# PCB_12V5A_60Wascii.net
KiCad netlist of a schematic drawn in Altium Designer
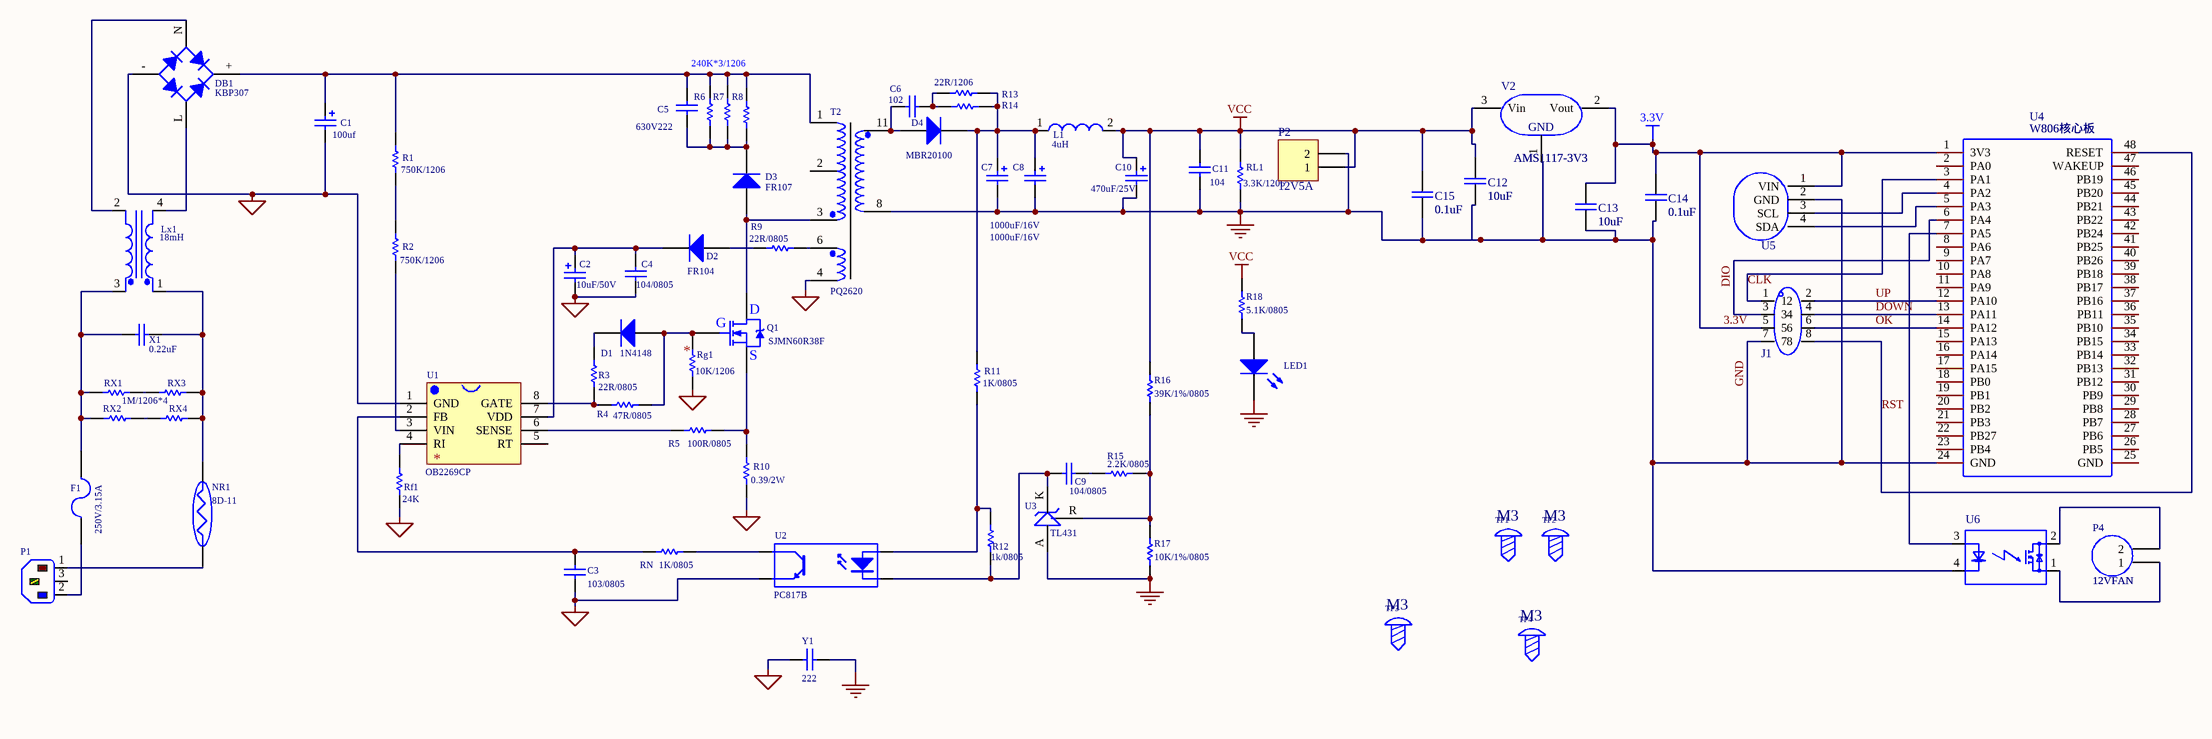
[diagram p0: PCB方案验证板  12V5A 60Wascii.SchDoc]

(export (version "E")
  (design (tool "Eeschema 10.0.6"))
  (components
    (comp (ref "C1")
      (value "100uf")
      (footprint "Cin /400V/56uF Wo")
      (description "Polarized Capacitor (Axial)")
      (fields (field (name "PUBLISHER") "Altium Limited"))
      (libsource (lib "") (part "Cap Pol2_1"))
    )
    (comp (ref "C2")
      (value "10uF/50V")
      (footprint "C Φ5*11 L=2.5")
      (description "Polarized Capacitor (Axial)")
      (fields (field (name "Comment") "47uF/50V") (field (name "PUBLISHER") "Altium Limited"))
      (libsource (lib "") (part "Cap Pol2_1"))
    )
    (comp (ref "C3")
      (value "103/0805")
      (footprint "0805-C")
      (description "Capacitor")
      (fields (field (name "PUBLISHER") "Altium Limited"))
      (libsource (lib "Miscellaneous Devices") (part "Cap"))
    )
    (comp (ref "C4")
      (value "104/0805")
      (footprint "0805-C")
      (description "Capacitor")
      (fields (field (name "PUBLISHER") "Altium Limited"))
      (libsource (lib "Miscellaneous Devices") (part "Cap"))
    )
    (comp (ref "C5")
      (value "630V222")
      (footprint "CBB=7.5MM")
      (description "Capacitor")
      (fields (field (name "PUBLISHER") "Altium Limited"))
      (libsource (lib "Miscellaneous Devices") (part "Cap"))
    )
    (comp (ref "C6")
      (value "102")
      (footprint "1206-C")
      (description "Capacitor")
      (fields (field (name "Comment") "472") (field (name "PUBLISHER") "Altium Limited"))
      (libsource (lib "Miscellaneous Devices") (part "Cap"))
    )
    (comp (ref "C7")
      (value "1000uF/16V")
      (footprint "C 1000UF/16V")
      (description "Polarized Capacitor (Axial)")
      (fields (field (name "PUBLISHER") "Altium Limited"))
      (libsource (lib "Miscellaneous Devices") (part "Cap Pol2"))
    )
    (comp (ref "C8")
      (value "1000uF/16V")
      (footprint "C 1000UF/16V")
      (description "Polarized Capacitor (Axial)")
      (fields (field (name "PUBLISHER") "Altium Limited"))
      (libsource (lib "Miscellaneous Devices") (part "Cap Pol2"))
    )
    (comp (ref "C9")
      (value "104/0805")
      (footprint "0805-C")
      (description "Capacitor")
      (fields (field (name "PUBLISHER") "Altium Limited"))
      (libsource (lib "Miscellaneous Devices") (part "Cap"))
    )
    (comp (ref "C10")
      (value "470uF/25V")
      (footprint "C= 3.5MM 8*15")
      (description "Polarized Capacitor (Axial)")
      (fields (field (name "PUBLISHER") "Altium Limited"))
      (libsource (lib "") (part "Cap Pol2_1"))
    )
    (comp (ref "C11")
      (value "104")
      (footprint "1206-C")
      (description "Capacitor")
      (fields (field (name "PUBLISHER") "Altium Limited"))
      (libsource (lib "Miscellaneous Devices") (part "Cap"))
    )
    (comp (ref "C12")
      (value "10uF")
      (footprint "0805-C")
      (fields (field (name "NAME") "10uF"))
      (libsource (lib "") (part "root_1_CAP-SMT__1"))
    )
    (comp (ref "C13")
      (value "10uF")
      (footprint "0805-C")
      (fields (field (name "NAME") "10uF"))
      (libsource (lib "") (part "root_1_CAP-SMT__1"))
    )
    (comp (ref "C14")
      (value "0.1uF")
      (footprint "0805-C")
      (fields (field (name "NAME") "0.1uF"))
      (libsource (lib "") (part "root_1_CAP-SMT__1"))
    )
    (comp (ref "C15")
      (value "0.1uF")
      (footprint "0805-C")
      (fields (field (name "NAME") "0.1uF"))
      (libsource (lib "altium-import") (part "root_1_CAP-SMT_"))
    )
    (comp (ref "D1")
      (value "1N4148")
      (footprint "D 1N4148")
      (description "Silicon Low Leakage Diode")
      (fields (field (name "PUBLISHER") "Altium Limited"))
      (libsource (lib "") (part "Diode BAS116_1"))
    )
    (comp (ref "D2")
      (value "FR104")
      (footprint "D/SOD123")
      (description "Silicon Low Leakage Diode")
      (fields (field (name "PUBLISHER") "Altium Limited"))
      (libsource (lib "Miscellaneous Devices") (part "Diode BAS116"))
    )
    (comp (ref "D3")
      (value "FR107")
      (footprint "D/SOD123")
      (description "Silicon Low Leakage Diode")
      (fields (field (name "PUBLISHER") "Altium Limited"))
      (libsource (lib "Miscellaneous Devices") (part "Diode BAS116"))
    )
    (comp (ref "D4")
      (value "MBR20100")
      (footprint "D TO-220")
      (description "Silicon Low Leakage Diode")
      (fields (field (name "PUBLISHER") "Altium Limited"))
      (libsource (lib "Miscellaneous Devices") (part "Diode BAS116"))
    )
    (comp (ref "DB1")
      (value "KBP307")
      (footprint "DB D=1.1MM")
      (description "Full Wave Diode Bridge")
      (fields (field (name "PUBLISHER") "Altium Limited"))
      (libsource (lib "Miscellaneous Devices") (part "Bridge1"))
    )
    (comp (ref "F1")
      (value "250V/3.15A")
      (footprint "F 3.15A L=5MM")
      (description "Fuse")
      (fields (field (name "PUBLISHER") "Altium Limited"))
      (libsource (lib "Miscellaneous Devices") (part "Fuse 2"))
    )
    (comp (ref "J1")
      (value "~")
      (footprint "HDR-TH_8P-P2.54-V-F-R2-C4-S2.54-1")
      (fields (field (name "MANUFACTURER PART") "2.54mm,24Doublerowfemale"))
      (libsource (lib "altium-import") (part "root_0_2.54mm,2×4Doublerowfemale_"))
    )
    (comp (ref "L1")
      (value "4uH")
      (footprint "L=7.6MM")
      (description "Inductor")
      (fields (field (name "PUBLISHER") "Altium Limited"))
      (libsource (lib "Miscellaneous Devices") (part "Inductor"))
    )
    (comp (ref "LED1")
      (value "LED1")
      (footprint "C0805")
      (description "Typical RED, GREEN, YELLOW, AMBER GaAs LED")
      (fields (field (name "PUBLISHER") "Altium Limited"))
      (libsource (lib "Miscellaneous Devices") (part "LED2"))
    )
    (comp (ref "Lx1")
      (value "18mH")
      (footprint "LF=6.9MM")
      (description "Transformer (Ideal)")
      (fields (field (name "PUBLISHER") "Altium Limited"))
      (libsource (lib "Miscellaneous Devices") (part "Trans Ideal"))
    )
    (comp (ref "NR1") (value "8D-11") (footprint "NTC=7.5mm") (libsource (lib "12V5A") (part "NTC")))
    (comp (ref "P1")
      (value "Plug AC Male")
      (footprint "KF128-3.81-2P")
      (description "IEC Mains Power Inlet, EN60 320-1 C14 Class I Cold Condition, PC Flange Rear Mount, Chassis Plug")
      (fields (field (name "PUBLISHER") "Altium Limited"))
      (libsource (lib "Miscellaneous Connectors") (part "Plug AC Male"))
    )
    (comp (ref "P2")
      (value "12V5A")
      (footprint "OUT")
      (description "Header, 2-Pin")
      (fields (field (name "PUBLISHER") "Altium Limited"))
      (libsource (lib "Miscellaneous Connectors") (part "Header 2"))
    )
    (comp (ref "P4")
      (value "12VFAN")
      (footprint "OUT")
      (fields (field (name "NAME") "12VFAN") (field (name "PUBLISHER") "Altium Limited"))
      (libsource (lib "altium-import") (part "root_2_12V5A_"))
    )
    (comp (ref "Q1")
      (value "SJMN60R38F")
      (footprint "MOSFET1")
      (description "N-Channel Power MOSFET")
      (fields (field (name "PUBLISHER") "Altium Limited"))
      (libsource (lib "Miscellaneous Devices") (part "NMOS-2"))
    )
    (comp (ref "R1")
      (value "750K/1206")
      (footprint "1206-R")
      (description "Resistor")
      (fields (field (name "PUBLISHER") "Altium Limited"))
      (libsource (lib "Miscellaneous Devices") (part "Res1"))
    )
    (comp (ref "R2")
      (value "750K/1206")
      (footprint "1206-R")
      (description "Resistor")
      (fields (field (name "PUBLISHER") "Altium Limited"))
      (libsource (lib "Miscellaneous Devices") (part "Res1"))
    )
    (comp (ref "R3")
      (value "22R/0805")
      (footprint "0805-R")
      (description "Resistor")
      (fields (field (name "PUBLISHER") "Altium Limited"))
      (libsource (lib "Miscellaneous Devices") (part "Res1"))
    )
    (comp (ref "R4")
      (value "47R/0805")
      (footprint "0805-R")
      (description "Resistor")
      (fields (field (name "PUBLISHER") "Altium Limited"))
      (libsource (lib "Miscellaneous Devices") (part "Res1"))
    )
    (comp (ref "R5")
      (value "100R/0805")
      (footprint "0805-R")
      (description "Resistor")
      (fields (field (name "PUBLISHER") "Altium Limited"))
      (libsource (lib "Miscellaneous Devices") (part "Res1"))
    )
    (comp (ref "R6")
      (value "50K/2510/1W")
      (footprint "1206-R")
      (description "Resistor")
      (fields (field (name "PUBLISHER") "Altium Limited"))
      (libsource (lib "Miscellaneous Devices") (part "Res1"))
    )
    (comp (ref "R7")
      (value "50K/2510/1W")
      (footprint "1206-R")
      (description "Resistor")
      (fields (field (name "PUBLISHER") "Altium Limited"))
      (libsource (lib "Miscellaneous Devices") (part "Res1"))
    )
    (comp (ref "R8")
      (value "50K/2510/1W")
      (footprint "1206-R")
      (description "Resistor")
      (fields (field (name "PUBLISHER") "Altium Limited"))
      (libsource (lib "Miscellaneous Devices") (part "Res1"))
    )
    (comp (ref "R9")
      (value "22R/0805")
      (footprint "0805-R")
      (description "Resistor")
      (fields (field (name "PUBLISHER") "Altium Limited"))
      (libsource (lib "Miscellaneous Devices") (part "Res1"))
    )
    (comp (ref "R10")
      (value "0.39/2W")
      (footprint "R  2W")
      (description "Resistor")
      (fields (field (name "PUBLISHER") "Altium Limited"))
      (libsource (lib "Miscellaneous Devices") (part "Res1"))
    )
    (comp (ref "R11")
      (value "1K/0805")
      (footprint "0805 RC")
      (description "Resistor")
      (fields (field (name "PUBLISHER") "Altium Limited"))
      (libsource (lib "Miscellaneous Devices") (part "Res1"))
    )
    (comp (ref "R12")
      (value "1k/0805")
      (footprint "0805-R")
      (description "Resistor")
      (fields (field (name "PUBLISHER") "Altium Limited"))
      (libsource (lib "Miscellaneous Devices") (part "Res1"))
    )
    (comp (ref "R13")
      (value "51R/1206")
      (footprint "1206-R")
      (description "Resistor")
      (fields (field (name "PUBLISHER") "Altium Limited"))
      (libsource (lib "Miscellaneous Devices") (part "Res1"))
    )
    (comp (ref "R14")
      (value "22R/1206")
      (footprint "1206-R")
      (description "Resistor")
      (fields (field (name "PUBLISHER") "Altium Limited"))
      (libsource (lib "Miscellaneous Devices") (part "Res1"))
    )
    (comp (ref "R15")
      (value "2.2K/0805")
      (footprint "0805-R")
      (description "Resistor")
      (fields (field (name "PUBLISHER") "Altium Limited"))
      (libsource (lib "Miscellaneous Devices") (part "Res1"))
    )
    (comp (ref "R16")
      (value "39K/1%/0805")
      (footprint "0805-R")
      (description "Resistor")
      (fields (field (name "PUBLISHER") "Altium Limited"))
      (libsource (lib "Miscellaneous Devices") (part "Res1"))
    )
    (comp (ref "R17")
      (value "10K/1%/0805")
      (footprint "0805-R")
      (description "Resistor")
      (fields (field (name "Comment") "12.5K/1%/0805") (field (name "PUBLISHER") "Altium Limited"))
      (libsource (lib "Miscellaneous Devices") (part "Res1"))
    )
    (comp (ref "R18")
      (value "5.1K/0805")
      (footprint "0805-R")
      (description "Resistor")
      (fields (field (name "PUBLISHER") "Altium Limited"))
      (libsource (lib "Miscellaneous Devices") (part "Res1"))
    )
    (comp (ref "Rf1")
      (value "24K")
      (footprint "0805-R")
      (description "Resistor")
      (fields (field (name "Comment") "Res1") (field (name "PUBLISHER") "Altium Limited"))
      (libsource (lib "Miscellaneous Devices") (part "Res1"))
    )
    (comp (ref "Rg1")
      (value "10K/1206")
      (footprint "0805-R")
      (description "Resistor")
      (fields (field (name "Comment") "10K/0805") (field (name "PUBLISHER") "Altium Limited"))
      (libsource (lib "Miscellaneous Devices") (part "Res1"))
    )
    (comp (ref "RL1")
      (value "3.3K/1206")
      (footprint "1206-R")
      (description "Resistor")
      (fields (field (name "PUBLISHER") "Altium Limited"))
      (libsource (lib "Miscellaneous Devices") (part "Res1"))
    )
    (comp (ref "RN")
      (value "1K/0805")
      (footprint "0805-R")
      (description "Resistor")
      (fields (field (name "PUBLISHER") "Altium Limited"))
      (libsource (lib "Miscellaneous Devices") (part "Res1"))
    )
    (comp (ref "RX1")
      (value "1M/1206*4")
      (footprint "1206-R")
      (description "Resistor")
      (fields (field (name "PUBLISHER") "Altium Limited"))
      (libsource (lib "Miscellaneous Devices") (part "Res1"))
    )
    (comp (ref "RX2")
      (value "1M/1206")
      (footprint "1206-R")
      (description "Resistor")
      (fields (field (name "PUBLISHER") "Altium Limited"))
      (libsource (lib "Miscellaneous Devices") (part "Res1"))
    )
    (comp (ref "RX3")
      (value "1M/1206")
      (footprint "1206-R")
      (description "Resistor")
      (fields (field (name "PUBLISHER") "Altium Limited"))
      (libsource (lib "Miscellaneous Devices") (part "Res1"))
    )
    (comp (ref "RX4")
      (value "1M/1206")
      (footprint "1206-R")
      (description "Resistor")
      (fields (field (name "PUBLISHER") "Altium Limited"))
      (libsource (lib "Miscellaneous Devices") (part "Res1"))
    )
    (comp (ref "T2") (value "PQ2620") (footprint "T PQ2620") (libsource (lib "12V5A") (part "T")))
    (comp (ref "TP1")
      (value "~")
      (footprint "M3x8+6_N")
      (libsource (lib "altium-import") (part "root_0_M3_"))
    )
    (comp (ref "TP2")
      (value "~")
      (footprint "M3x8+6_N")
      (libsource (lib "altium-import") (part "root_0_M3_"))
    )
    (comp (ref "TP3")
      (value "~")
      (footprint "M3x8+6_N")
      (libsource (lib "altium-import") (part "root_0_M3_"))
    )
    (comp (ref "TP4")
      (value "~")
      (footprint "M3x8+6_N")
      (libsource (lib "altium-import") (part "root_0_M3_"))
    )
    (comp (ref "U1") (value "OB2269CP") (footprint "OB2269") (libsource (lib "12V5A") (part "OB2269CP")))
    (comp (ref "U2")
      (value "PC817B")
      (footprint "LC-SMD-4")
      (description "4-Pin Phototransistor Optocoupler")
      (fields (field (name "PUBLISHER") "Altium Limited"))
      (libsource (lib "Miscellaneous Devices") (part "Optoisolator1"))
    )
    (comp (ref "U3")
      (value "TL431")
      (footprint "LC-SOT-23(SOT-23-3)")
      (libsource (lib "12V5A") (part "TL431"))
    )
    (comp (ref "U4")
      (value "W806核心板")
      (footprint "w806")
      (fields (field (name "NAME") "W806核心板"))
      (libsource (lib "altium-import") (part "root_0_W806核心板_"))
    )
    (comp (ref "U5")
      (value "~")
      (footprint "AHT10")
      (libsource (lib "altium-import") (part "root_0_AHT10温湿度传感器_"))
    )
    (comp (ref "U6")
      (value "~")
      (footprint "w806:RELAY-TH_4P-L43.5-W10.3-PMN")
      (fields (field (name "MANUFACTURER") "PANASONIC(松下)") (field (name "MANUFACTURER PART") "AQZ102D"))
      (libsource (lib "altium-import") (part "root_0_PMN5D6132_ENMG_"))
    )
    (comp (ref "V2")
      (value "AMS1117-3V3")
      (footprint "PG-SOT223-4_L6.5-W3.5-P2.30-LS7.0-BR")
      (fields (field (name "NAME") "AMS1117-3V3"))
      (libsource (lib "altium-import") (part "root_0_AMS1117_"))
    )
    (comp (ref "X1")
      (value "0.22uF")
      (footprint "CX=10mm")
      (description "Capacitor")
      (fields (field (name "Comment") "224") (field (name "PUBLISHER") "Altium Limited"))
      (libsource (lib "Miscellaneous Devices") (part "Cap"))
    )
    (comp (ref "Y1")
      (value "222")
      (footprint "Y1")
      (description "Capacitor")
      (fields (field (name "PUBLISHER") "Altium Limited"))
      (libsource (lib "Miscellaneous Devices") (part "Cap"))
    )
  )
  (nets
    (net (code "1") (name "/CLK") (class "Default")
      (node (ref "J1") (pin "1") (pinfunction "1_1") (pintype "passive"))
      (node (ref "U4") (pin "3") (pinfunction "PA1_3") (pintype "passive"))
    )
    (net (code "2") (name "/DIO") (class "Default")
      (node (ref "J1") (pin "3") (pinfunction "3_3") (pintype "passive"))
      (node (ref "U4") (pin "6") (pinfunction "PA4_6") (pintype "passive"))
    )
    (net (code "3") (name "/DOWN") (class "Default")
      (node (ref "J1") (pin "4") (pinfunction "4_4") (pintype "passive"))
      (node (ref "U4") (pin "13") (pinfunction "PA11_13") (pintype "passive"))
    )
    (net (code "4") (name "/OK") (class "Default")
      (node (ref "J1") (pin "6") (pinfunction "6_6") (pintype "passive"))
      (node (ref "U4") (pin "14") (pinfunction "PA12_14") (pintype "passive"))
    )
    (net (code "5") (name "/RST") (class "Default")
      (node (ref "J1") (pin "8") (pinfunction "8_8") (pintype "passive"))
      (node (ref "U4") (pin "48") (pinfunction "RESET_48") (pintype "passive"))
    )
    (net (code "6") (name "/UP") (class "Default")
      (node (ref "J1") (pin "2") (pinfunction "2_2") (pintype "passive"))
      (node (ref "U4") (pin "12") (pinfunction "PA10_12") (pintype "passive"))
    )
    (net (code "7") (name "3.3V") (class "Default")
      (node (ref "C13") (pin "2") (pinfunction "2_2") (pintype "passive"))
      (node (ref "C14") (pin "2") (pinfunction "2_2") (pintype "passive"))
      (node (ref "J1") (pin "5") (pinfunction "5_5") (pintype "passive"))
      (node (ref "U4") (pin "1") (pinfunction "3V3_1") (pintype "passive"))
      (node (ref "U5") (pin "1") (pinfunction "VIN_1") (pintype "passive"))
      (node (ref "V2") (pin "2") (pinfunction "Vout_2") (pintype "passive"))
    )
    (net (code "8") (name "GND") (class "Default")
      (node (ref "C10") (pin "2") (pinfunction "2_2") (pintype "passive"))
      (node (ref "C11") (pin "2") (pinfunction "2_2") (pintype "passive"))
      (node (ref "C12") (pin "1") (pinfunction "1_1") (pintype "passive"))
      (node (ref "C13") (pin "1") (pinfunction "1_1") (pintype "passive"))
      (node (ref "C14") (pin "1") (pinfunction "1_1") (pintype "passive"))
      (node (ref "C15") (pin "1") (pinfunction "1_1") (pintype "passive"))
      (node (ref "C7") (pin "1") (pinfunction "1_1") (pintype "passive"))
      (node (ref "C8") (pin "1") (pinfunction "1_1") (pintype "passive"))
      (node (ref "J1") (pin "7") (pinfunction "7_7") (pintype "passive"))
      (node (ref "LED1") (pin "2") (pinfunction "K_2") (pintype "passive"))
      (node (ref "P2") (pin "GND") (pinfunction "2_GND") (pintype "passive"))
      (node (ref "R17") (pin "1") (pinfunction "1_1") (pintype "passive"))
      (node (ref "RL1") (pin "1") (pinfunction "1_1") (pintype "passive"))
      (node (ref "T2") (pin "8") (pintype "passive"))
      (node (ref "U3") (pin "A") (pinfunction "A_A") (pintype "passive"))
      (node (ref "U4") (pin "24") (pinfunction "GND_24") (pintype "passive"))
      (node (ref "U5") (pin "2") (pinfunction "GND_2") (pintype "passive"))
      (node (ref "U6") (pin "4") (pinfunction "+_4") (pintype "passive"))
      (node (ref "V2") (pin "1") (pinfunction "GND_1") (pintype "passive"))
      (node (ref "Y1") (pin "2") (pinfunction "2_2") (pintype "passive"))
    )
    (net (code "9") (name "GND1") (class "Default")
      (node (ref "C1") (pin "2") (pinfunction "2_2") (pintype "passive"))
      (node (ref "C2") (pin "2") (pinfunction "2_2") (pintype "passive"))
      (node (ref "C3") (pin "1") (pinfunction "1_1") (pintype "passive"))
      (node (ref "C4") (pin "2") (pinfunction "2_2") (pintype "passive"))
      (node (ref "DB1") (pin "-") (pinfunction "2_-") (pintype "passive"))
      (node (ref "R10") (pin "1") (pinfunction "1_1") (pintype "passive"))
      (node (ref "Rf1") (pin "2") (pinfunction "2_2") (pintype "passive"))
      (node (ref "Rg1") (pin "2") (pinfunction "2_2") (pintype "passive"))
      (node (ref "T2") (pin "4") (pinfunction "4_4") (pintype "passive"))
      (node (ref "U1") (pin "1") (pinfunction "GND_1") (pintype "passive"))
      (node (ref "U2") (pin "E") (pinfunction "E_E") (pintype "passive"))
      (node (ref "Y1") (pin "1") (pinfunction "1_1") (pintype "passive"))
    )
    (net (code "10") (name "Net-(C6-Pad2)") (class "Default")
      (node (ref "C6") (pin "2") (pinfunction "2_2") (pintype "passive"))
      (node (ref "R13") (pin "2") (pinfunction "2_2") (pintype "passive"))
      (node (ref "R14") (pin "2") (pinfunction "2_2") (pintype "passive"))
    )
    (net (code "11") (name "Net-(C9-Pad1)") (class "Default")
      (node (ref "C9") (pin "1") (pinfunction "1_1") (pintype "passive"))
      (node (ref "R12") (pin "1") (pinfunction "1_1") (pintype "passive"))
      (node (ref "U2") (pin "K") (pinfunction "K_K") (pintype "passive"))
      (node (ref "U3") (pin "K") (pinfunction "K_K") (pintype "passive"))
    )
    (net (code "12") (name "Net-(C9-Pad2)") (class "Default")
      (node (ref "C9") (pin "2") (pinfunction "2_2") (pintype "passive"))
      (node (ref "R15") (pin "2") (pinfunction "2_2") (pintype "passive"))
    )
    (net (code "13") (name "Net-(D1-A)") (class "Default")
      (node (ref "D1") (pin "+") (pinfunction "A_+") (pintype "passive"))
      (node (ref "Q1") (pin "G") (pinfunction "G_G") (pintype "passive"))
      (node (ref "R4") (pin "1") (pinfunction "1_1") (pintype "passive"))
      (node (ref "Rg1") (pin "1") (pinfunction "1_1") (pintype "passive"))
    )
    (net (code "14") (name "Net-(D1-K)") (class "Default")
      (node (ref "D1") (pin "-") (pinfunction "K_-") (pintype "passive"))
      (node (ref "R3") (pin "1") (pinfunction "1_1") (pintype "passive"))
    )
    (net (code "15") (name "Net-(D2-A)") (class "Default")
      (node (ref "D2") (pin "1") (pinfunction "A_1") (pintype "passive"))
      (node (ref "R9") (pin "2") (pinfunction "2_2") (pintype "passive"))
    )
    (net (code "16") (name "Net-(D2-K)") (class "Default")
      (node (ref "C2") (pin "1") (pinfunction "1_1") (pintype "passive"))
      (node (ref "C4") (pin "1") (pinfunction "1_1") (pintype "passive"))
      (node (ref "D2") (pin "2") (pinfunction "K_2") (pintype "passive"))
      (node (ref "U1") (pin "7") (pinfunction "VDD_7") (pintype "passive"))
    )
    (net (code "17") (name "Net-(D3-A)") (class "Default")
      (node (ref "D3") (pin "1") (pinfunction "A_1") (pintype "passive"))
      (node (ref "Q1") (pin "D") (pinfunction "D_D") (pintype "passive"))
      (node (ref "T2") (pin "3") (pintype "passive"))
    )
    (net (code "18") (name "Net-(D3-K)") (class "Default")
      (node (ref "C5") (pin "2") (pinfunction "2_2") (pintype "passive"))
      (node (ref "D3") (pin "2") (pinfunction "K_2") (pintype "passive"))
      (node (ref "R6") (pin "2") (pinfunction "2_2") (pintype "passive"))
      (node (ref "R7") (pin "2") (pinfunction "2_2") (pintype "passive"))
      (node (ref "R8") (pin "2") (pinfunction "2_2") (pintype "passive"))
    )
    (net (code "19") (name "Net-(D4-A)") (class "Default")
      (node (ref "C6") (pin "1") (pinfunction "1_1") (pintype "passive"))
      (node (ref "D4") (pin "1") (pinfunction "A_1") (pintype "passive"))
      (node (ref "T2") (pin "11") (pinfunction "6_11") (pintype "passive"))
    )
    (net (code "20") (name "Net-(D4-K)") (class "Default")
      (node (ref "C7") (pin "2") (pinfunction "2_2") (pintype "passive"))
      (node (ref "C8") (pin "2") (pinfunction "2_2") (pintype "passive"))
      (node (ref "D4") (pin "2") (pinfunction "K_2") (pintype "passive"))
      (node (ref "L1") (pin "1") (pinfunction "1_1") (pintype "passive"))
      (node (ref "R11") (pin "2") (pinfunction "2_2") (pintype "passive"))
      (node (ref "R13") (pin "1") (pinfunction "1_1") (pintype "passive"))
      (node (ref "R14") (pin "1") (pinfunction "1_1") (pintype "passive"))
    )
    (net (code "21") (name "Net-(DB1-1)") (class "Default")
      (node (ref "C1") (pin "1") (pinfunction "1_1") (pintype "passive"))
      (node (ref "C5") (pin "1") (pinfunction "1_1") (pintype "passive"))
      (node (ref "DB1") (pin "+") (pinfunction "1_+") (pintype "passive"))
      (node (ref "R1") (pin "2") (pinfunction "2_2") (pintype "passive"))
      (node (ref "R6") (pin "1") (pinfunction "1_1") (pintype "passive"))
      (node (ref "R7") (pin "1") (pinfunction "1_1") (pintype "passive"))
      (node (ref "R8") (pin "1") (pinfunction "1_1") (pintype "passive"))
      (node (ref "T2") (pin "1") (pintype "passive"))
    )
    (net (code "22") (name "Net-(DB1-3)") (class "Default")
      (node (ref "DB1") (pin "N") (pinfunction "3_N") (pintype "passive"))
      (node (ref "Lx1") (pin "2") (pinfunction "Sec-_2") (pintype "passive"))
    )
    (net (code "23") (name "Net-(DB1-4)") (class "Default")
      (node (ref "DB1") (pin "L") (pinfunction "4_L") (pintype "passive"))
      (node (ref "Lx1") (pin "4") (pinfunction "Pri-_4") (pintype "passive"))
    )
    (net (code "24") (name "Net-(LED1-A)") (class "Default")
      (node (ref "LED1") (pin "1") (pinfunction "A_1") (pintype "passive"))
      (node (ref "R18") (pin "1") (pinfunction "1_1") (pintype "passive"))
    )
    (net (code "25") (name "Net-(Lx1-Pri+)") (class "Default")
      (node (ref "Lx1") (pin "1") (pinfunction "Pri+_1") (pintype "passive"))
      (node (ref "NR1") (pin "1") (pinfunction "1_1") (pintype "passive"))
      (node (ref "RX3") (pin "2") (pinfunction "2_2") (pintype "passive"))
      (node (ref "RX4") (pin "2") (pinfunction "2_2") (pintype "passive"))
      (node (ref "X1") (pin "2") (pinfunction "2_2") (pintype "passive"))
    )
    (net (code "26") (name "Net-(Lx1-Sec+)") (class "Default")
      (node (ref "F1") (pin "2") (pinfunction "2_2") (pintype "passive"))
      (node (ref "Lx1") (pin "3") (pinfunction "Sec+_3") (pintype "passive"))
      (node (ref "RX1") (pin "1") (pinfunction "1_1") (pintype "passive"))
      (node (ref "RX2") (pin "1") (pinfunction "1_1") (pintype "passive"))
      (node (ref "X1") (pin "1") (pinfunction "1_1") (pintype "passive"))
    )
    (net (code "27") (name "Net-(P1-L)") (class "Default")
      (node (ref "NR1") (pin "2") (pinfunction "2_2") (pintype "passive"))
      (node (ref "P1") (pin "1") (pinfunction "L_1") (pintype "power_in"))
    )
    (net (code "28") (name "Net-(P1-N)") (class "Default")
      (node (ref "F1") (pin "1") (pinfunction "1_1") (pintype "passive"))
      (node (ref "P1") (pin "2") (pinfunction "N_2") (pintype "power_in"))
    )
    (net (code "29") (name "Net-(P4-1)") (class "Default")
      (node (ref "P4") (pin "VCC") (pinfunction "1_VCC") (pintype "passive"))
      (node (ref "U6") (pin "1") (pinfunction "K_1") (pintype "passive"))
    )
    (net (code "30") (name "Net-(P4-2)") (class "Default")
      (node (ref "P4") (pin "GND") (pinfunction "2_GND") (pintype "passive"))
      (node (ref "U6") (pin "2") (pinfunction "A_2") (pintype "passive"))
    )
    (net (code "31") (name "Net-(Q1-PadS)") (class "Default")
      (node (ref "Q1") (pin "S") (pinfunction "S_S") (pintype "passive"))
      (node (ref "R10") (pin "2") (pinfunction "2_2") (pintype "passive"))
      (node (ref "R5") (pin "1") (pinfunction "1_1") (pintype "passive"))
    )
    (net (code "32") (name "Net-(R1-Pad1)") (class "Default")
      (node (ref "R1") (pin "1") (pinfunction "1_1") (pintype "passive"))
      (node (ref "R2") (pin "2") (pinfunction "2_2") (pintype "passive"))
    )
    (net (code "33") (name "Net-(R9-Pad1)") (class "Default")
      (node (ref "R9") (pin "1") (pinfunction "1_1") (pintype "passive"))
      (node (ref "T2") (pin "6") (pintype "passive"))
    )
    (net (code "34") (name "Net-(R11-Pad1)") (class "Default")
      (node (ref "R11") (pin "1") (pinfunction "1_1") (pintype "passive"))
      (node (ref "R12") (pin "2") (pinfunction "2_2") (pintype "passive"))
      (node (ref "U2") (pin "A") (pinfunction "A_A") (pintype "passive"))
    )
    (net (code "35") (name "Net-(R15-Pad1)") (class "Default")
      (node (ref "R15") (pin "1") (pinfunction "1_1") (pintype "passive"))
      (node (ref "R16") (pin "1") (pinfunction "1_1") (pintype "passive"))
      (node (ref "R17") (pin "2") (pinfunction "2_2") (pintype "passive"))
      (node (ref "U3") (pin "R") (pinfunction "R_R") (pintype "passive"))
    )
    (net (code "36") (name "Net-(RN-Pad1)") (class "Default")
      (node (ref "RN") (pin "1") (pinfunction "1_1") (pintype "passive"))
      (node (ref "U2") (pin "C") (pinfunction "C_C") (pintype "passive"))
    )
    (net (code "37") (name "Net-(RX1-Pad2)") (class "Default")
      (node (ref "RX1") (pin "2") (pinfunction "2_2") (pintype "passive"))
      (node (ref "RX3") (pin "1") (pinfunction "1_1") (pintype "passive"))
    )
    (net (code "38") (name "Net-(RX2-Pad2)") (class "Default")
      (node (ref "RX2") (pin "2") (pinfunction "2_2") (pintype "passive"))
      (node (ref "RX4") (pin "1") (pinfunction "1_1") (pintype "passive"))
    )
    (net (code "39") (name "Net-(U1-FB)") (class "Default")
      (node (ref "C3") (pin "2") (pinfunction "2_2") (pintype "passive"))
      (node (ref "RN") (pin "2") (pinfunction "2_2") (pintype "passive"))
      (node (ref "U1") (pin "2") (pinfunction "FB_2") (pintype "passive"))
    )
    (net (code "40") (name "Net-(U1-GATE)") (class "Default")
      (node (ref "R3") (pin "2") (pinfunction "2_2") (pintype "passive"))
      (node (ref "R4") (pin "2") (pinfunction "2_2") (pintype "passive"))
      (node (ref "U1") (pin "8") (pinfunction "GATE_8") (pintype "passive"))
    )
    (net (code "41") (name "Net-(U1-RI)") (class "Default")
      (node (ref "Rf1") (pin "1") (pinfunction "1_1") (pintype "passive"))
      (node (ref "U1") (pin "4") (pinfunction "RI_4") (pintype "passive"))
    )
    (net (code "42") (name "Net-(U1-SENSE)") (class "Default")
      (node (ref "R5") (pin "2") (pinfunction "2_2") (pintype "passive"))
      (node (ref "U1") (pin "6") (pinfunction "SENSE_6") (pintype "passive"))
    )
    (net (code "43") (name "Net-(U1-VIN)") (class "Default")
      (node (ref "R2") (pin "1") (pinfunction "1_1") (pintype "passive"))
      (node (ref "U1") (pin "3") (pinfunction "VIN_3") (pintype "passive"))
    )
    (net (code "44") (name "Net-(U4-PA2)") (class "Default")
      (node (ref "U4") (pin "4") (pinfunction "PA2_4") (pintype "passive"))
      (node (ref "U5") (pin "3") (pinfunction "SCL_3") (pintype "passive"))
    )
    (net (code "45") (name "Net-(U4-PA3)") (class "Default")
      (node (ref "U4") (pin "5") (pinfunction "PA3_5") (pintype "passive"))
      (node (ref "U5") (pin "4") (pinfunction "SDA_4") (pintype "passive"))
    )
    (net (code "46") (name "Net-(U4-PA5)") (class "Default")
      (node (ref "U4") (pin "7") (pinfunction "PA5_7") (pintype "passive"))
      (node (ref "U6") (pin "3") (pinfunction "-_3") (pintype "passive"))
    )
    (net (code "47") (name "VCC") (class "Default")
      (node (ref "C10") (pin "1") (pinfunction "1_1") (pintype "passive"))
      (node (ref "C11") (pin "1") (pinfunction "1_1") (pintype "passive"))
      (node (ref "C12") (pin "2") (pinfunction "2_2") (pintype "passive"))
      (node (ref "C15") (pin "2") (pinfunction "2_2") (pintype "passive"))
      (node (ref "L1") (pin "2") (pinfunction "2_2") (pintype "passive"))
      (node (ref "P2") (pin "VCC") (pinfunction "1_VCC") (pintype "passive"))
      (node (ref "R16") (pin "2") (pinfunction "2_2") (pintype "passive"))
      (node (ref "R18") (pin "2") (pinfunction "2_2") (pintype "passive"))
      (node (ref "RL1") (pin "2") (pinfunction "2_2") (pintype "passive"))
      (node (ref "V2") (pin "3") (pinfunction "Vin_3") (pintype "passive"))
    )
    (net (code "48") (name "unconnected-(P1-E-Pad3)") (class "Default")
      (node (ref "P1") (pin "3") (pinfunction "E_3") (pintype "power_in"))
    )
    (net (code "49") (name "unconnected-(T2-Pad2)") (class "Default")
      (node (ref "T2") (pin "2") (pintype "passive"))
    )
    (net (code "50") (name "unconnected-(U1-RT-Pad5)") (class "Default")
      (node (ref "U1") (pin "5") (pinfunction "RT_5") (pintype "passive"))
    )
    (net (code "51") (name "unconnected-(U4-GND-Pad25)") (class "Default")
      (node (ref "U4") (pin "25") (pinfunction "GND_25") (pintype "passive"))
    )
    (net (code "52") (name "unconnected-(U4-PA0-Pad2)") (class "Default")
      (node (ref "U4") (pin "2") (pinfunction "PA0_2") (pintype "passive"))
    )
    (net (code "53") (name "unconnected-(U4-PA6-Pad8)") (class "Default")
      (node (ref "U4") (pin "8") (pinfunction "PA6_8") (pintype "passive"))
    )
    (net (code "54") (name "unconnected-(U4-PA7-Pad9)") (class "Default")
      (node (ref "U4") (pin "9") (pinfunction "PA7_9") (pintype "passive"))
    )
    (net (code "55") (name "unconnected-(U4-PA8-Pad10)") (class "Default")
      (node (ref "U4") (pin "10") (pinfunction "PA8_10") (pintype "passive"))
    )
    (net (code "56") (name "unconnected-(U4-PA9-Pad11)") (class "Default")
      (node (ref "U4") (pin "11") (pinfunction "PA9_11") (pintype "passive"))
    )
    (net (code "57") (name "unconnected-(U4-PA13-Pad15)") (class "Default")
      (node (ref "U4") (pin "15") (pinfunction "PA13_15") (pintype "passive"))
    )
    (net (code "58") (name "unconnected-(U4-PA14-Pad16)") (class "Default")
      (node (ref "U4") (pin "16") (pinfunction "PA14_16") (pintype "passive"))
    )
    (net (code "59") (name "unconnected-(U4-PA15-Pad17)") (class "Default")
      (node (ref "U4") (pin "17") (pinfunction "PA15_17") (pintype "passive"))
    )
    (net (code "60") (name "unconnected-(U4-PB0-Pad18)") (class "Default")
      (node (ref "U4") (pin "18") (pinfunction "PB0_18") (pintype "passive"))
    )
    (net (code "61") (name "unconnected-(U4-PB1-Pad19)") (class "Default")
      (node (ref "U4") (pin "19") (pinfunction "PB1_19") (pintype "passive"))
    )
    (net (code "62") (name "unconnected-(U4-PB2-Pad20)") (class "Default")
      (node (ref "U4") (pin "20") (pinfunction "PB2_20") (pintype "passive"))
    )
    (net (code "63") (name "unconnected-(U4-PB3-Pad21)") (class "Default")
      (node (ref "U4") (pin "21") (pinfunction "PB3_21") (pintype "passive"))
    )
    (net (code "64") (name "unconnected-(U4-PB4-Pad23)") (class "Default")
      (node (ref "U4") (pin "23") (pinfunction "PB4_23") (pintype "passive"))
    )
    (net (code "65") (name "unconnected-(U4-PB5-Pad26)") (class "Default")
      (node (ref "U4") (pin "26") (pinfunction "PB5_26") (pintype "passive"))
    )
    (net (code "66") (name "unconnected-(U4-PB6-Pad27)") (class "Default")
      (node (ref "U4") (pin "27") (pinfunction "PB6_27") (pintype "passive"))
    )
    (net (code "67") (name "unconnected-(U4-PB7-Pad28)") (class "Default")
      (node (ref "U4") (pin "28") (pinfunction "PB7_28") (pintype "passive"))
    )
    (net (code "68") (name "unconnected-(U4-PB8-Pad29)") (class "Default")
      (node (ref "U4") (pin "29") (pinfunction "PB8_29") (pintype "passive"))
    )
    (net (code "69") (name "unconnected-(U4-PB9-Pad30)") (class "Default")
      (node (ref "U4") (pin "30") (pinfunction "PB9_30") (pintype "passive"))
    )
    (net (code "70") (name "unconnected-(U4-PB10-Pad35)") (class "Default")
      (node (ref "U4") (pin "35") (pinfunction "PB10_35") (pintype "passive"))
    )
    (net (code "71") (name "unconnected-(U4-PB11-Pad36)") (class "Default")
      (node (ref "U4") (pin "36") (pinfunction "PB11_36") (pintype "passive"))
    )
    (net (code "72") (name "unconnected-(U4-PB12-Pad31)") (class "Default")
      (node (ref "U4") (pin "31") (pinfunction "PB12_31") (pintype "passive"))
    )
    (net (code "73") (name "unconnected-(U4-PB13-Pad32)") (class "Default")
      (node (ref "U4") (pin "32") (pinfunction "PB13_32") (pintype "passive"))
    )
    (net (code "74") (name "unconnected-(U4-PB14-Pad33)") (class "Default")
      (node (ref "U4") (pin "33") (pinfunction "PB14_33") (pintype "passive"))
    )
    (net (code "75") (name "unconnected-(U4-PB15-Pad34)") (class "Default")
      (node (ref "U4") (pin "34") (pinfunction "PB15_34") (pintype "passive"))
    )
    (net (code "76") (name "unconnected-(U4-PB16-Pad37)") (class "Default")
      (node (ref "U4") (pin "37") (pinfunction "PB16_37") (pintype "passive"))
    )
    (net (code "77") (name "unconnected-(U4-PB17-Pad38)") (class "Default")
      (node (ref "U4") (pin "38") (pinfunction "PB17_38") (pintype "passive"))
    )
    (net (code "78") (name "unconnected-(U4-PB18-Pad39)") (class "Default")
      (node (ref "U4") (pin "39") (pinfunction "PB18_39") (pintype "passive"))
    )
    (net (code "79") (name "unconnected-(U4-PB19-Pad46)") (class "Default")
      (node (ref "U4") (pin "46") (pinfunction "PB19_46") (pintype "passive"))
    )
    (net (code "80") (name "unconnected-(U4-PB20-Pad45)") (class "Default")
      (node (ref "U4") (pin "45") (pinfunction "PB20_45") (pintype "passive"))
    )
    (net (code "81") (name "unconnected-(U4-PB21-Pad44)") (class "Default")
      (node (ref "U4") (pin "44") (pinfunction "PB21_44") (pintype "passive"))
    )
    (net (code "82") (name "unconnected-(U4-PB22-Pad43)") (class "Default")
      (node (ref "U4") (pin "43") (pinfunction "PB22_43") (pintype "passive"))
    )
    (net (code "83") (name "unconnected-(U4-PB24-Pad42)") (class "Default")
      (node (ref "U4") (pin "42") (pinfunction "PB24_42") (pintype "passive"))
    )
    (net (code "84") (name "unconnected-(U4-PB25-Pad41)") (class "Default")
      (node (ref "U4") (pin "41") (pinfunction "PB25_41") (pintype "passive"))
    )
    (net (code "85") (name "unconnected-(U4-PB26-Pad40)") (class "Default")
      (node (ref "U4") (pin "40") (pinfunction "PB26_40") (pintype "passive"))
    )
    (net (code "86") (name "unconnected-(U4-PB27-Pad22)") (class "Default")
      (node (ref "U4") (pin "22") (pinfunction "PB27_22") (pintype "passive"))
    )
    (net (code "87") (name "unconnected-(U4-WAKEUP-Pad47)") (class "Default")
      (node (ref "U4") (pin "47") (pinfunction "WAKEUP_47") (pintype "passive"))
    )
  )
)
